# tix_clock.net
KiCad netlist of a schematic drawn in EAGLE
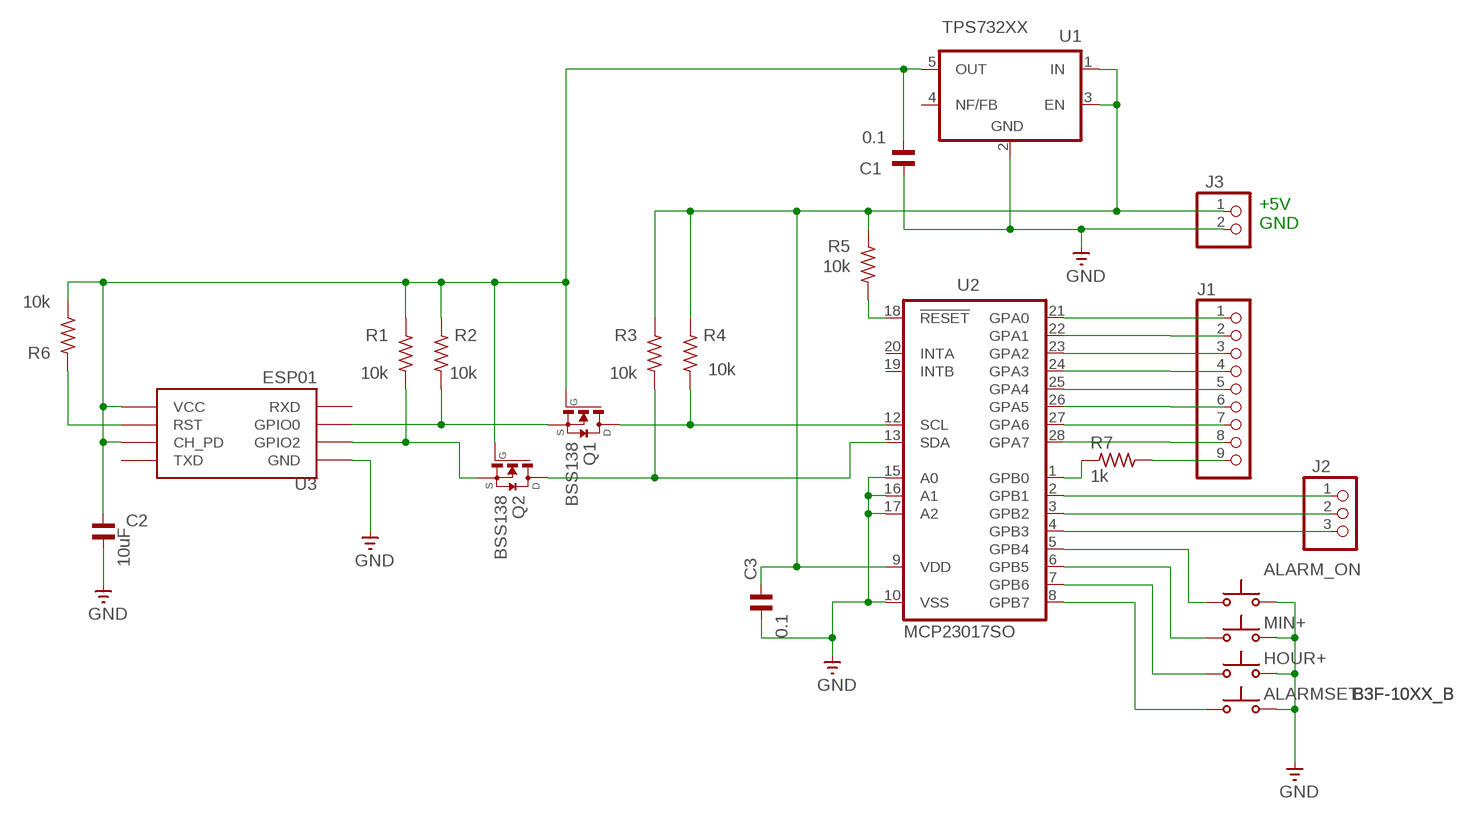
[diagram p0: schematic, sheet 1]

(export (version "E")
  (design (tool "Eeschema 10.0.6"))
  (components
    (comp (ref "ALARMSET")
      (value "B3F-10XX_B")
      (footprint "eagle-import:B3F-10XX_B")
      (libsource (lib "eagle-import") (part "B3F-10XX_B"))
    )
    (comp (ref "ALARM_ON")
      (value "B3F-10XX_B")
      (footprint "eagle-import:B3F-10XX_B")
      (libsource (lib "eagle-import") (part "B3F-10XX_B"))
    )
    (comp (ref "C1")
      (value "0.1")
      (footprint "eagle-import:C0805")
      (libsource (lib "eagle-import") (part "C-USC0805"))
    )
    (comp (ref "C2")
      (value "10uF")
      (footprint "eagle-import:C0805")
      (libsource (lib "eagle-import") (part "C-USC0805"))
    )
    (comp (ref "C3")
      (value "0.1")
      (footprint "eagle-import:C0805")
      (libsource (lib "eagle-import") (part "C-USC0805"))
    )
    (comp (ref "HOUR+")
      (value "B3F-10XX_B")
      (footprint "eagle-import:B3F-10XX_B")
      (libsource (lib "eagle-import") (part "B3F-10XX_B"))
    )
    (comp (ref "J1")
      (value "PINHD-1X9")
      (footprint "eagle-import:1X09")
      (libsource (lib "eagle-import") (part "PINHD-1X9"))
    )
    (comp (ref "J2")
      (value "PINHD-1X3")
      (footprint "eagle-import:1X03")
      (libsource (lib "eagle-import") (part "PINHD-1X3"))
    )
    (comp (ref "J3")
      (value "PINHD-1X2")
      (footprint "eagle-import:1X02")
      (libsource (lib "eagle-import") (part "PINHD-1X2"))
    )
    (comp (ref "MIN+")
      (value "B3F-10XX_B")
      (footprint "eagle-import:B3F-10XX_B")
      (libsource (lib "eagle-import") (part "B3F-10XX_B"))
    )
    (comp (ref "Q1")
      (value "BSS138")
      (footprint "eagle-import:SOT23")
      (libsource (lib "eagle-import") (part "BSS138"))
    )
    (comp (ref "Q2")
      (value "BSS138")
      (footprint "eagle-import:SOT23")
      (libsource (lib "eagle-import") (part "BSS138"))
    )
    (comp (ref "R1")
      (value "10k")
      (footprint "eagle-import:R0805")
      (libsource (lib "eagle-import") (part "R_0805"))
    )
    (comp (ref "R2")
      (value "10k")
      (footprint "eagle-import:R0805")
      (libsource (lib "eagle-import") (part "R_0805"))
    )
    (comp (ref "R3")
      (value "10k")
      (footprint "eagle-import:R0805")
      (libsource (lib "eagle-import") (part "R_0805"))
    )
    (comp (ref "R4")
      (value "10k")
      (footprint "eagle-import:R0805")
      (libsource (lib "eagle-import") (part "R_0805"))
    )
    (comp (ref "R5")
      (value "10k")
      (footprint "eagle-import:R0805")
      (libsource (lib "eagle-import") (part "R_0805"))
    )
    (comp (ref "R6")
      (value "10k")
      (footprint "eagle-import:R0805")
      (libsource (lib "eagle-import") (part "R_0805"))
    )
    (comp (ref "R7")
      (value "1k")
      (footprint "eagle-import:R0805")
      (libsource (lib "eagle-import") (part "R-US_R0805"))
    )
    (comp (ref "U1")
      (value "TPS732XX")
      (footprint "eagle-import:SOT23-5")
      (libsource (lib "eagle-import") (part "TPS732XX"))
    )
    (comp (ref "U2")
      (value "MCP23017SO")
      (footprint "eagle-import:SO28W")
      (libsource (lib "eagle-import") (part "MCP23017SO"))
    )
    (comp (ref "U3")
      (value "ESP01")
      (footprint "eagle-import:ESP01")
      (libsource (lib "eagle-import") (part "ESP01"))
    )
  )
  (nets
    (net (code "1") (name "GND") (class "Default")
      (node (ref "ALARMSET") (pin "3") (pinfunction "S_3") (pintype "passive"))
      (node (ref "ALARMSET") (pin "4") (pinfunction "S_4") (pintype "passive"))
      (node (ref "ALARM_ON") (pin "3") (pinfunction "S_3") (pintype "passive"))
      (node (ref "ALARM_ON") (pin "4") (pinfunction "S_4") (pintype "passive"))
      (node (ref "C1") (pin "2") (pinfunction "2_2") (pintype "passive"))
      (node (ref "C2") (pin "2") (pinfunction "2_2") (pintype "passive"))
      (node (ref "C3") (pin "2") (pinfunction "2_2") (pintype "passive"))
      (node (ref "HOUR+") (pin "3") (pinfunction "S_3") (pintype "passive"))
      (node (ref "HOUR+") (pin "4") (pinfunction "S_4") (pintype "passive"))
      (node (ref "J3") (pin "2") (pinfunction "2_2") (pintype "passive"))
      (node (ref "MIN+") (pin "3") (pinfunction "S_3") (pintype "passive"))
      (node (ref "MIN+") (pin "4") (pinfunction "S_4") (pintype "passive"))
      (node (ref "U1") (pin "2") (pinfunction "GND_2") (pintype "power_in"))
      (node (ref "U2") (pin "10") (pinfunction "VSS_10") (pintype "power_in"))
      (node (ref "U2") (pin "15") (pinfunction "A0_15") (pintype "input"))
      (node (ref "U2") (pin "16") (pinfunction "A1_16") (pintype "input"))
      (node (ref "U2") (pin "17") (pinfunction "A2_17") (pintype "input"))
      (node (ref "U3") (pin "GND") (pinfunction "GND_GND") (pintype "bidirectional"))
    )
    (net (code "2") (name "Net-(J1-Pad9)") (class "Default")
      (node (ref "J1") (pin "9") (pinfunction "9_9") (pintype "passive"))
      (node (ref "R7") (pin "2") (pinfunction "2_2") (pintype "passive"))
    )
    (net (code "3") (name "Net-(Q1-D)") (class "Default")
      (node (ref "Q1") (pin "3") (pinfunction "D_3") (pintype "passive"))
      (node (ref "R4") (pin "1") (pinfunction "1_1") (pintype "passive"))
      (node (ref "U2") (pin "12") (pinfunction "SCL_12") (pintype "input"))
    )
    (net (code "4") (name "Net-(Q1-G)") (class "Default")
      (node (ref "C1") (pin "1") (pinfunction "1_1") (pintype "passive"))
      (node (ref "C2") (pin "1") (pinfunction "1_1") (pintype "passive"))
      (node (ref "Q1") (pin "1") (pinfunction "G_1") (pintype "passive"))
      (node (ref "Q2") (pin "1") (pinfunction "G_1") (pintype "passive"))
      (node (ref "R1") (pin "2") (pinfunction "2_2") (pintype "passive"))
      (node (ref "R2") (pin "2") (pinfunction "2_2") (pintype "passive"))
      (node (ref "R6") (pin "2") (pinfunction "2_2") (pintype "passive"))
      (node (ref "U1") (pin "5") (pinfunction "OUT_5") (pintype "passive"))
      (node (ref "U3") (pin "CH_PD") (pinfunction "CH_PD_CH_PD") (pintype "bidirectional"))
      (node (ref "U3") (pin "VCC") (pinfunction "VCC_VCC") (pintype "bidirectional"))
    )
    (net (code "5") (name "Net-(Q1-S)") (class "Default")
      (node (ref "Q1") (pin "2") (pinfunction "S_2") (pintype "passive"))
      (node (ref "R2") (pin "1") (pinfunction "1_1") (pintype "passive"))
      (node (ref "U3") (pin "GPIO0") (pinfunction "GPIO0_GPIO0") (pintype "bidirectional"))
    )
    (net (code "6") (name "Net-(Q2-D)") (class "Default")
      (node (ref "Q2") (pin "3") (pinfunction "D_3") (pintype "passive"))
      (node (ref "R3") (pin "1") (pinfunction "1_1") (pintype "passive"))
      (node (ref "U2") (pin "13") (pinfunction "SDA_13") (pintype "bidirectional"))
    )
    (net (code "7") (name "Net-(Q2-S)") (class "Default")
      (node (ref "Q2") (pin "2") (pinfunction "S_2") (pintype "passive"))
      (node (ref "R1") (pin "1") (pinfunction "1_1") (pintype "passive"))
      (node (ref "U3") (pin "GPIO2") (pinfunction "GPIO2_GPIO2") (pintype "bidirectional"))
    )
    (net (code "8") (name "Net-(R6-Pad1)") (class "Default")
      (node (ref "R6") (pin "1") (pinfunction "1_1") (pintype "passive"))
      (node (ref "U3") (pin "RST") (pinfunction "RST_RST") (pintype "bidirectional"))
    )
    (net (code "9") (name "Net-(U1-EN)") (class "Default")
      (node (ref "C3") (pin "1") (pinfunction "1_1") (pintype "passive"))
      (node (ref "J3") (pin "1") (pinfunction "1_1") (pintype "passive"))
      (node (ref "R3") (pin "2") (pinfunction "2_2") (pintype "passive"))
      (node (ref "R4") (pin "2") (pinfunction "2_2") (pintype "passive"))
      (node (ref "R5") (pin "2") (pinfunction "2_2") (pintype "passive"))
      (node (ref "U1") (pin "1") (pinfunction "IN_1") (pintype "input"))
      (node (ref "U1") (pin "3") (pinfunction "EN_3") (pintype "input"))
      (node (ref "U2") (pin "9") (pinfunction "VDD_9") (pintype "power_in"))
    )
    (net (code "10") (name "Net-(U2-GPA0)") (class "Default")
      (node (ref "J1") (pin "1") (pinfunction "1_1") (pintype "passive"))
      (node (ref "U2") (pin "21") (pinfunction "GPA0_21") (pintype "bidirectional"))
    )
    (net (code "11") (name "Net-(U2-GPA1)") (class "Default")
      (node (ref "J1") (pin "2") (pinfunction "2_2") (pintype "passive"))
      (node (ref "U2") (pin "22") (pinfunction "GPA1_22") (pintype "bidirectional"))
    )
    (net (code "12") (name "Net-(U2-GPA2)") (class "Default")
      (node (ref "J1") (pin "3") (pinfunction "3_3") (pintype "passive"))
      (node (ref "U2") (pin "23") (pinfunction "GPA2_23") (pintype "bidirectional"))
    )
    (net (code "13") (name "Net-(U2-GPA3)") (class "Default")
      (node (ref "J1") (pin "4") (pinfunction "4_4") (pintype "passive"))
      (node (ref "U2") (pin "24") (pinfunction "GPA3_24") (pintype "bidirectional"))
    )
    (net (code "14") (name "Net-(U2-GPA4)") (class "Default")
      (node (ref "J1") (pin "5") (pinfunction "5_5") (pintype "passive"))
      (node (ref "U2") (pin "25") (pinfunction "GPA4_25") (pintype "bidirectional"))
    )
    (net (code "15") (name "Net-(U2-GPA5)") (class "Default")
      (node (ref "J1") (pin "6") (pinfunction "6_6") (pintype "passive"))
      (node (ref "U2") (pin "26") (pinfunction "GPA5_26") (pintype "bidirectional"))
    )
    (net (code "16") (name "Net-(U2-GPA6)") (class "Default")
      (node (ref "J1") (pin "7") (pinfunction "7_7") (pintype "passive"))
      (node (ref "U2") (pin "27") (pinfunction "GPA6_27") (pintype "bidirectional"))
    )
    (net (code "17") (name "Net-(U2-GPA7)") (class "Default")
      (node (ref "J1") (pin "8") (pinfunction "8_8") (pintype "passive"))
      (node (ref "U2") (pin "28") (pinfunction "GPA7_28") (pintype "bidirectional"))
    )
    (net (code "18") (name "Net-(U2-GPB0)") (class "Default")
      (node (ref "R7") (pin "1") (pinfunction "1_1") (pintype "passive"))
      (node (ref "U2") (pin "1") (pinfunction "GPB0_1") (pintype "bidirectional"))
    )
    (net (code "19") (name "Net-(U2-GPB1)") (class "Default")
      (node (ref "J2") (pin "1") (pinfunction "1_1") (pintype "passive"))
      (node (ref "U2") (pin "2") (pinfunction "GPB1_2") (pintype "bidirectional"))
    )
    (net (code "20") (name "Net-(U2-GPB2)") (class "Default")
      (node (ref "J2") (pin "2") (pinfunction "2_2") (pintype "passive"))
      (node (ref "U2") (pin "3") (pinfunction "GPB2_3") (pintype "bidirectional"))
    )
    (net (code "21") (name "Net-(U2-GPB3)") (class "Default")
      (node (ref "J2") (pin "3") (pinfunction "3_3") (pintype "passive"))
      (node (ref "U2") (pin "4") (pinfunction "GPB3_4") (pintype "bidirectional"))
    )
    (net (code "22") (name "Net-(U2-GPB4)") (class "Default")
      (node (ref "ALARM_ON") (pin "1") (pinfunction "P_1") (pintype "passive"))
      (node (ref "ALARM_ON") (pin "2") (pinfunction "P_2") (pintype "passive"))
      (node (ref "U2") (pin "5") (pinfunction "GPB4_5") (pintype "bidirectional"))
    )
    (net (code "23") (name "Net-(U2-GPB5)") (class "Default")
      (node (ref "MIN+") (pin "1") (pinfunction "P_1") (pintype "passive"))
      (node (ref "MIN+") (pin "2") (pinfunction "P_2") (pintype "passive"))
      (node (ref "U2") (pin "6") (pinfunction "GPB5_6") (pintype "bidirectional"))
    )
    (net (code "24") (name "Net-(U2-GPB6)") (class "Default")
      (node (ref "HOUR+") (pin "1") (pinfunction "P_1") (pintype "passive"))
      (node (ref "HOUR+") (pin "2") (pinfunction "P_2") (pintype "passive"))
      (node (ref "U2") (pin "7") (pinfunction "GPB6_7") (pintype "bidirectional"))
    )
    (net (code "25") (name "Net-(U2-GPB7)") (class "Default")
      (node (ref "ALARMSET") (pin "1") (pinfunction "P_1") (pintype "passive"))
      (node (ref "ALARMSET") (pin "2") (pinfunction "P_2") (pintype "passive"))
      (node (ref "U2") (pin "8") (pinfunction "GPB7_8") (pintype "bidirectional"))
    )
    (net (code "26") (name "Net-(U2-~{RESET})") (class "Default")
      (node (ref "R5") (pin "1") (pinfunction "1_1") (pintype "passive"))
      (node (ref "U2") (pin "18") (pinfunction "~{RESET}_18") (pintype "input"))
    )
    (net (code "27") (name "unconnected-(U1-NF{slash}FB-Pad4)") (class "Default")
      (node (ref "U1") (pin "4") (pinfunction "NF/FB_4") (pintype "passive"))
    )
    (net (code "28") (name "unconnected-(U2-INTA-Pad20)") (class "Default")
      (node (ref "U2") (pin "20") (pinfunction "INTA_20") (pintype "output"))
    )
    (net (code "29") (name "unconnected-(U2-INTB-Pad19)") (class "Default")
      (node (ref "U2") (pin "19") (pinfunction "INTB_19") (pintype "output"))
    )
    (net (code "30") (name "unconnected-(U3-RXD-PadRX)") (class "Default")
      (node (ref "U3") (pin "RX") (pinfunction "RXD_RX") (pintype "bidirectional"))
    )
    (net (code "31") (name "unconnected-(U3-TXD-PadTX)") (class "Default")
      (node (ref "U3") (pin "TX") (pinfunction "TXD_TX") (pintype "bidirectional"))
    )
  )
)
